# supply.net
KiCad netlist of a schematic drawn in EAGLE
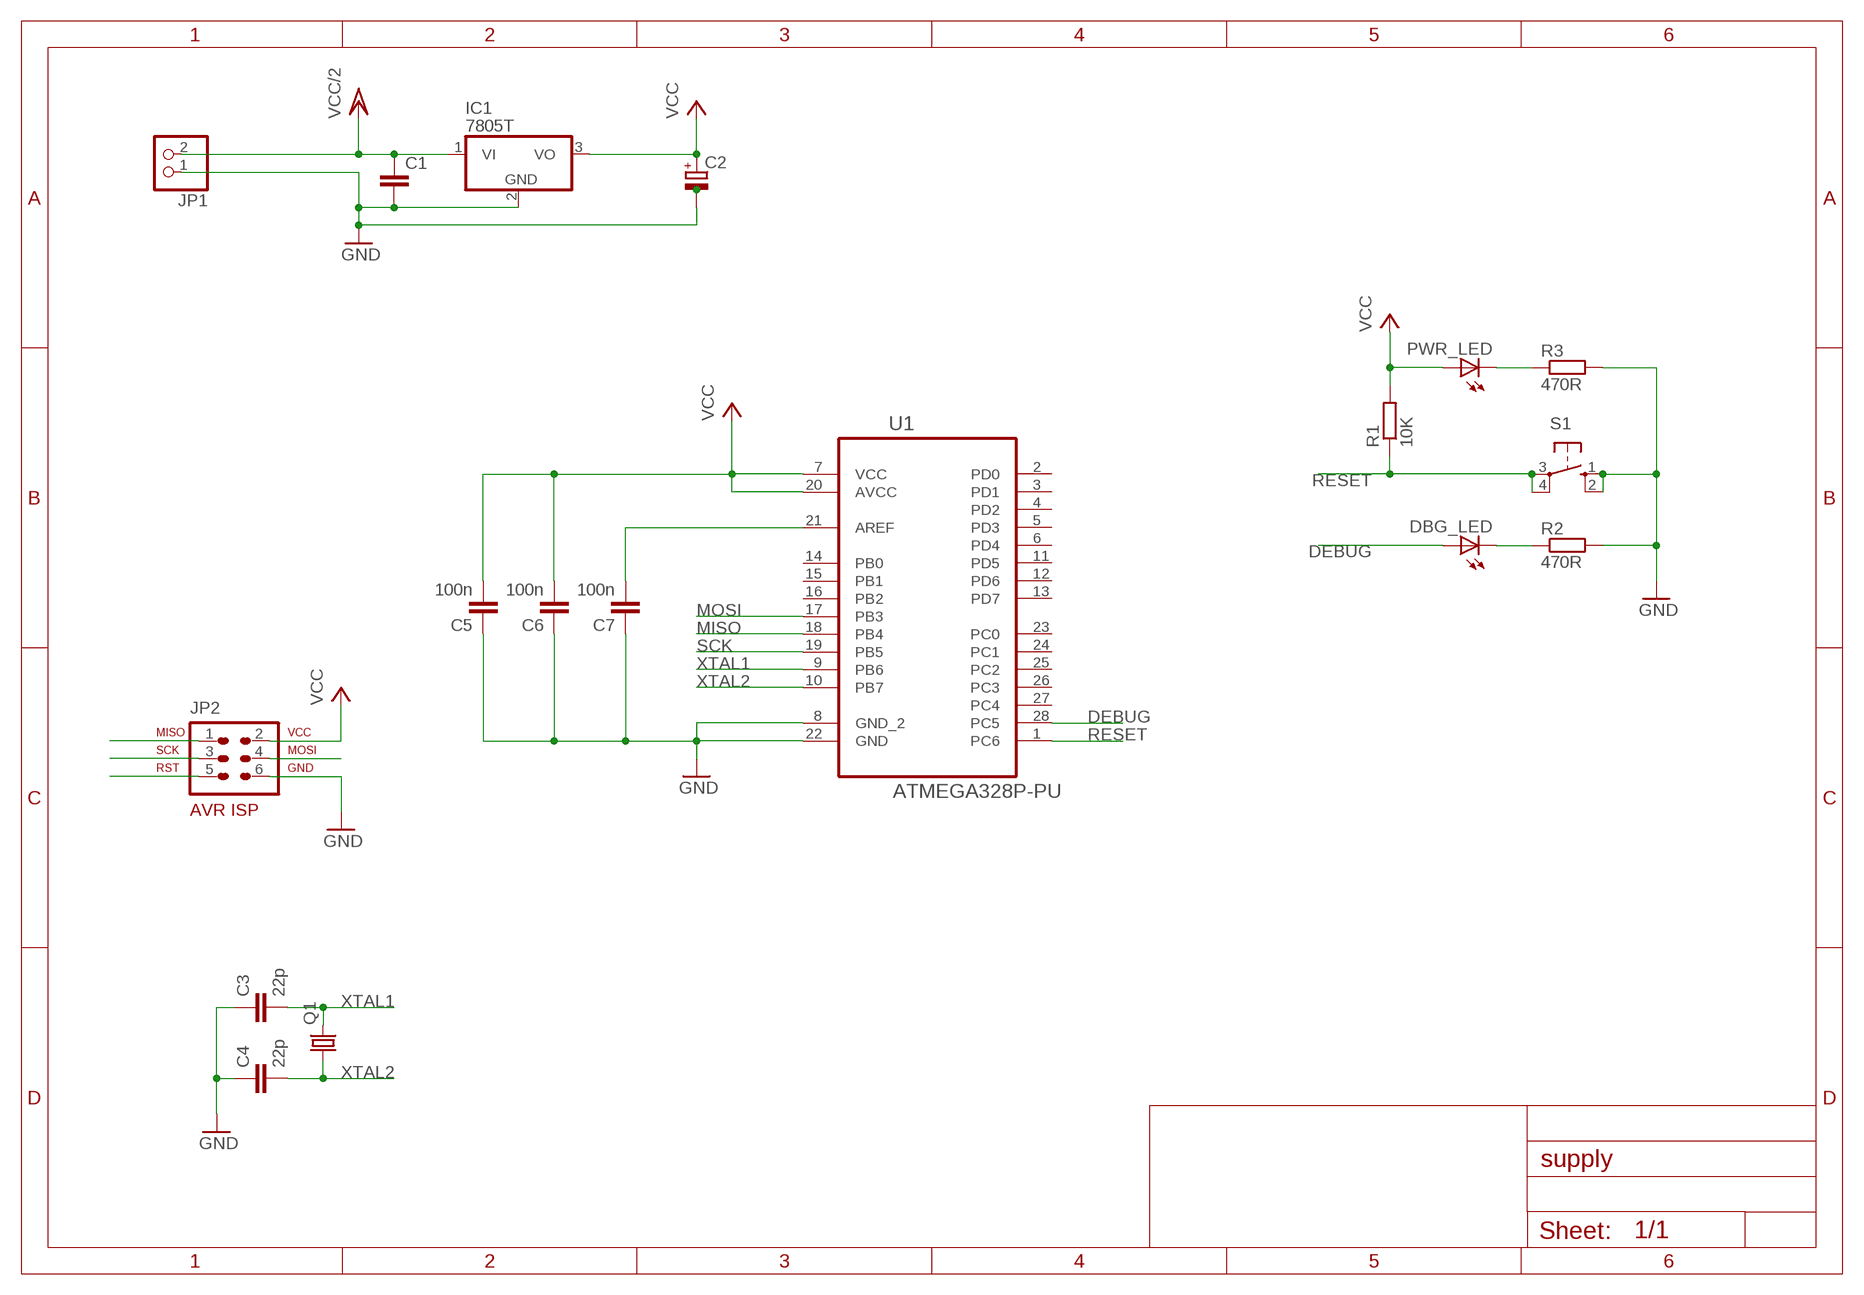
[diagram p0: schematic, sheet 1]

(export (version "E")
  (design (tool "Eeschema 10.0.6"))
  (components
    (comp (ref "C1")
      (value "C-EUC1206K")
      (footprint "eagle-import:C1206K")
      (libsource (lib "eagle-import") (part "C-EUC1206K"))
    )
    (comp (ref "C2")
      (value "CPOL-EUE2.5-5")
      (footprint "eagle-import:E2,5-5")
      (libsource (lib "eagle-import") (part "CPOL-EUE2.5-5"))
    )
    (comp (ref "C3")
      (value "22p")
      (footprint "eagle-import:C0805K")
      (libsource (lib "eagle-import") (part "C-EUC0805K"))
    )
    (comp (ref "C4")
      (value "22p")
      (footprint "eagle-import:C0805K")
      (libsource (lib "eagle-import") (part "C-EUC0805K"))
    )
    (comp (ref "C5")
      (value "100n")
      (footprint "eagle-import:C0805K")
      (libsource (lib "eagle-import") (part "C-EUC0805K"))
    )
    (comp (ref "C6")
      (value "100n")
      (footprint "eagle-import:C0805K")
      (libsource (lib "eagle-import") (part "C-EUC0805K"))
    )
    (comp (ref "C7")
      (value "100n")
      (footprint "eagle-import:C0805K")
      (libsource (lib "eagle-import") (part "C-EUC0805K"))
    )
    (comp (ref "DBG_LED")
      (value "LED5MM")
      (footprint "eagle-import:LED5MM")
      (libsource (lib "eagle-import") (part "LED5MM"))
    )
    (comp (ref "IC1")
      (value "7805T")
      (footprint "eagle-import:TO220H")
      (libsource (lib "eagle-import") (part "78T05"))
    )
    (comp (ref "JP1")
      (value "PINHD-1X2")
      (footprint "eagle-import:1X02")
      (libsource (lib "eagle-import") (part "PINHD-1X2"))
    )
    (comp (ref "JP2")
      (value "AVR-ISP-6VERT")
      (footprint "eagle-import:AVR-ISP-6")
      (libsource (lib "eagle-import") (part "AVR-ISP-6VERT"))
    )
    (comp (ref "PWR_LED")
      (value "LED5MM")
      (footprint "eagle-import:LED5MM")
      (libsource (lib "eagle-import") (part "LED5MM"))
    )
    (comp (ref "Q1")
      (value "CRYSTALHC49S")
      (footprint "eagle-import:HC49_S")
      (libsource (lib "eagle-import") (part "CRYSTALHC49S"))
    )
    (comp (ref "R1")
      (value "10K")
      (footprint "eagle-import:M0805")
      (libsource (lib "eagle-import") (part "R-EU_M0805"))
    )
    (comp (ref "R2")
      (value "470R")
      (footprint "eagle-import:M0805")
      (libsource (lib "eagle-import") (part "R-EU_M0805"))
    )
    (comp (ref "R3")
      (value "470R")
      (footprint "eagle-import:M0805")
      (libsource (lib "eagle-import") (part "R-EU_M0805"))
    )
    (comp (ref "S1")
      (value "10-XX")
      (footprint "eagle-import:B3F-10XX")
      (fields (field (name "MPN") "B3F-1000"))
      (libsource (lib "eagle-import") (part "10-XX"))
    )
    (comp (ref "U1")
      (value "ATMEGA328P-PU")
      (footprint "eagle-import:DIP254P762X457-28")
      (libsource (lib "eagle-import") (part "ATMEGA328P-PU"))
    )
  )
  (nets
    (net (code "1") (name "/DEBUG") (class "Default")
      (node (ref "DBG_LED") (pin "A") (pinfunction "A_A") (pintype "passive"))
      (node (ref "U1") (pin "28") (pinfunction "PC5_28") (pintype "bidirectional"))
    )
    (net (code "2") (name "/MISO") (class "Default")
      (node (ref "JP2") (pin "1") (pinfunction "1_1") (pintype "passive"))
      (node (ref "U1") (pin "18") (pinfunction "PB4_18") (pintype "bidirectional"))
    )
    (net (code "3") (name "/MOSI") (class "Default")
      (node (ref "JP2") (pin "4") (pinfunction "4_4") (pintype "passive"))
      (node (ref "U1") (pin "17") (pinfunction "PB3_17") (pintype "bidirectional"))
    )
    (net (code "4") (name "/RESET") (class "Default")
      (node (ref "JP2") (pin "5") (pinfunction "5_5") (pintype "passive"))
      (node (ref "R1") (pin "1") (pinfunction "1_1") (pintype "passive"))
      (node (ref "S1") (pin "3") (pinfunction "P_3") (pintype "passive"))
      (node (ref "S1") (pin "4") (pinfunction "P1_4") (pintype "passive"))
      (node (ref "U1") (pin "1") (pinfunction "PC6_1") (pintype "bidirectional"))
    )
    (net (code "5") (name "/SCK") (class "Default")
      (node (ref "JP2") (pin "3") (pinfunction "3_3") (pintype "passive"))
      (node (ref "U1") (pin "19") (pinfunction "PB5_19") (pintype "bidirectional"))
    )
    (net (code "6") (name "/XTAL1") (class "Default")
      (node (ref "C3") (pin "2") (pinfunction "2_2") (pintype "passive"))
      (node (ref "Q1") (pin "2") (pinfunction "2_2") (pintype "passive"))
      (node (ref "U1") (pin "9") (pinfunction "PB6_9") (pintype "bidirectional"))
    )
    (net (code "7") (name "/XTAL2") (class "Default")
      (node (ref "C4") (pin "2") (pinfunction "2_2") (pintype "passive"))
      (node (ref "Q1") (pin "1") (pinfunction "1_1") (pintype "passive"))
      (node (ref "U1") (pin "10") (pinfunction "PB7_10") (pintype "bidirectional"))
    )
    (net (code "8") (name "GND") (class "Default")
      (node (ref "C1") (pin "2") (pinfunction "2_2") (pintype "passive"))
      (node (ref "C2") (pin "-") (pinfunction "-_-") (pintype "passive"))
      (node (ref "C3") (pin "1") (pinfunction "1_1") (pintype "passive"))
      (node (ref "C4") (pin "1") (pinfunction "1_1") (pintype "passive"))
      (node (ref "C5") (pin "1") (pinfunction "1_1") (pintype "passive"))
      (node (ref "C6") (pin "1") (pinfunction "1_1") (pintype "passive"))
      (node (ref "C7") (pin "1") (pinfunction "1_1") (pintype "passive"))
      (node (ref "IC1") (pin "2") (pinfunction "GND_2") (pintype "passive"))
      (node (ref "JP1") (pin "1") (pinfunction "1_1") (pintype "passive"))
      (node (ref "JP2") (pin "6") (pinfunction "6_6") (pintype "passive"))
      (node (ref "R2") (pin "2") (pinfunction "2_2") (pintype "passive"))
      (node (ref "R3") (pin "2") (pinfunction "2_2") (pintype "passive"))
      (node (ref "S1") (pin "1") (pinfunction "S_1") (pintype "passive"))
      (node (ref "S1") (pin "2") (pinfunction "S1_2") (pintype "passive"))
      (node (ref "U1") (pin "22") (pinfunction "GND_22") (pintype "passive"))
      (node (ref "U1") (pin "8") (pinfunction "GND_2_8") (pintype "passive"))
    )
    (net (code "9") (name "Net-(DBG_LED-C)") (class "Default")
      (node (ref "DBG_LED") (pin "K") (pinfunction "C_K") (pintype "passive"))
      (node (ref "R2") (pin "1") (pinfunction "1_1") (pintype "passive"))
    )
    (net (code "10") (name "Net-(PWR_LED-C)") (class "Default")
      (node (ref "PWR_LED") (pin "K") (pinfunction "C_K") (pintype "passive"))
      (node (ref "R3") (pin "1") (pinfunction "1_1") (pintype "passive"))
    )
    (net (code "11") (name "Net-(U1-AREF)") (class "Default")
      (node (ref "C7") (pin "2") (pinfunction "2_2") (pintype "passive"))
      (node (ref "U1") (pin "21") (pinfunction "AREF_21") (pintype "input"))
    )
    (net (code "12") (name "VCC") (class "Default")
      (node (ref "C2") (pin "+") (pinfunction "+_+") (pintype "passive"))
      (node (ref "C5") (pin "2") (pinfunction "2_2") (pintype "passive"))
      (node (ref "C6") (pin "2") (pinfunction "2_2") (pintype "passive"))
      (node (ref "IC1") (pin "3") (pinfunction "VO_3") (pintype "passive"))
      (node (ref "JP2") (pin "2") (pinfunction "2_2") (pintype "passive"))
      (node (ref "PWR_LED") (pin "A") (pinfunction "A_A") (pintype "passive"))
      (node (ref "R1") (pin "2") (pinfunction "2_2") (pintype "passive"))
      (node (ref "U1") (pin "20") (pinfunction "AVCC_20") (pintype "power_in"))
      (node (ref "U1") (pin "7") (pinfunction "VCC_7") (pintype "power_in"))
    )
    (net (code "13") (name "VCC{slash}2") (class "Default")
      (node (ref "C1") (pin "1") (pinfunction "1_1") (pintype "passive"))
      (node (ref "IC1") (pin "1") (pinfunction "VI_1") (pintype "input"))
      (node (ref "JP1") (pin "2") (pinfunction "2_2") (pintype "passive"))
    )
    (net (code "14") (name "unconnected-(U1-PB0-Pad14)") (class "Default")
      (node (ref "U1") (pin "14") (pinfunction "PB0_14") (pintype "bidirectional"))
    )
    (net (code "15") (name "unconnected-(U1-PB1-Pad15)") (class "Default")
      (node (ref "U1") (pin "15") (pinfunction "PB1_15") (pintype "bidirectional"))
    )
    (net (code "16") (name "unconnected-(U1-PB2-Pad16)") (class "Default")
      (node (ref "U1") (pin "16") (pinfunction "PB2_16") (pintype "bidirectional"))
    )
    (net (code "17") (name "unconnected-(U1-PC0-Pad23)") (class "Default")
      (node (ref "U1") (pin "23") (pinfunction "PC0_23") (pintype "bidirectional"))
    )
    (net (code "18") (name "unconnected-(U1-PC1-Pad24)") (class "Default")
      (node (ref "U1") (pin "24") (pinfunction "PC1_24") (pintype "bidirectional"))
    )
    (net (code "19") (name "unconnected-(U1-PC2-Pad25)") (class "Default")
      (node (ref "U1") (pin "25") (pinfunction "PC2_25") (pintype "bidirectional"))
    )
    (net (code "20") (name "unconnected-(U1-PC3-Pad26)") (class "Default")
      (node (ref "U1") (pin "26") (pinfunction "PC3_26") (pintype "bidirectional"))
    )
    (net (code "21") (name "unconnected-(U1-PC4-Pad27)") (class "Default")
      (node (ref "U1") (pin "27") (pinfunction "PC4_27") (pintype "bidirectional"))
    )
    (net (code "22") (name "unconnected-(U1-PD0-Pad2)") (class "Default")
      (node (ref "U1") (pin "2") (pinfunction "PD0_2") (pintype "bidirectional"))
    )
    (net (code "23") (name "unconnected-(U1-PD1-Pad3)") (class "Default")
      (node (ref "U1") (pin "3") (pinfunction "PD1_3") (pintype "bidirectional"))
    )
    (net (code "24") (name "unconnected-(U1-PD2-Pad4)") (class "Default")
      (node (ref "U1") (pin "4") (pinfunction "PD2_4") (pintype "bidirectional"))
    )
    (net (code "25") (name "unconnected-(U1-PD3-Pad5)") (class "Default")
      (node (ref "U1") (pin "5") (pinfunction "PD3_5") (pintype "bidirectional"))
    )
    (net (code "26") (name "unconnected-(U1-PD4-Pad6)") (class "Default")
      (node (ref "U1") (pin "6") (pinfunction "PD4_6") (pintype "bidirectional"))
    )
    (net (code "27") (name "unconnected-(U1-PD5-Pad11)") (class "Default")
      (node (ref "U1") (pin "11") (pinfunction "PD5_11") (pintype "bidirectional"))
    )
    (net (code "28") (name "unconnected-(U1-PD6-Pad12)") (class "Default")
      (node (ref "U1") (pin "12") (pinfunction "PD6_12") (pintype "bidirectional"))
    )
    (net (code "29") (name "unconnected-(U1-PD7-Pad13)") (class "Default")
      (node (ref "U1") (pin "13") (pinfunction "PD7_13") (pintype "bidirectional"))
    )
  )
)
